# schematic.net
KiCad netlist of a schematic drawn in EAGLE
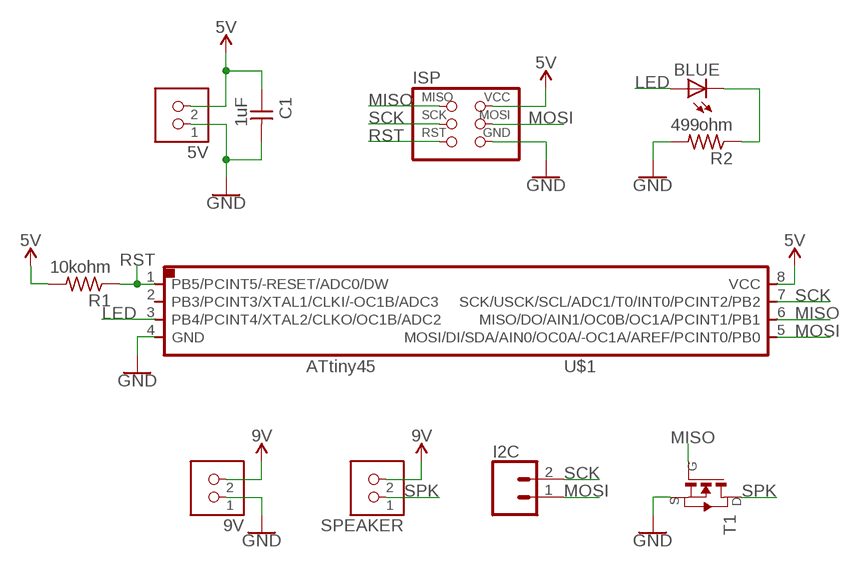
[diagram p0: schematic, sheet 1]

(export (version "E")
  (design (tool "Eeschema 10.0.6"))
  (components
    (comp (ref "5V")
      (value "TERM-1X02-FABLAB")
      (footprint "eagle-import:ED555DS-2DS")
      (libsource (lib "eagle-import") (part "TERM-1X02-FABLAB"))
    )
    (comp (ref "9V")
      (value "TERM-1X02-FABLAB")
      (footprint "eagle-import:ED555DS-2DS")
      (libsource (lib "eagle-import") (part "TERM-1X02-FABLAB"))
    )
    (comp (ref "BLUE")
      (value "LEDFAB1206")
      (footprint "eagle-import:LED1206FAB")
      (libsource (lib "eagle-import") (part "LEDFAB1206"))
    )
    (comp (ref "C1")
      (value "1uF")
      (footprint "eagle-import:C1206FAB")
      (libsource (lib "eagle-import") (part "CAP-UNPOLARIZEDFAB"))
    )
    (comp (ref "I2C")
      (value "CONN_021X02_NO_SILK")
      (footprint "eagle-import:1X02_NO_SILK")
      (libsource (lib "eagle-import") (part "CONN_021X02_NO_SILK"))
    )
    (comp (ref "ISP")
      (value "AVRISPSMD")
      (footprint "eagle-import:2X03SMD")
      (libsource (lib "eagle-import") (part "AVRISPSMD"))
    )
    (comp (ref "R1")
      (value "10kohm")
      (footprint "eagle-import:R1206FAB")
      (libsource (lib "eagle-import") (part "RES-US1206FAB"))
    )
    (comp (ref "R2")
      (value "499ohm")
      (footprint "eagle-import:R1206FAB")
      (libsource (lib "eagle-import") (part "RES-US1206FAB"))
    )
    (comp (ref "SPEAKER")
      (value "TERM-1X02-FABLAB")
      (footprint "eagle-import:ED555DS-2DS")
      (libsource (lib "eagle-import") (part "TERM-1X02-FABLAB"))
    )
    (comp (ref "T1")
      (value "NMOSFETSOT23")
      (footprint "eagle-import:SOT-23")
      (libsource (lib "eagle-import") (part "NMOSFETSOT23"))
    )
    (comp (ref "U$1")
      (value "ATTINY45SI")
      (footprint "eagle-import:SOIC8")
      (libsource (lib "eagle-import") (part "ATTINY45SI"))
    )
  )
  (nets
    (net (code "1") (name "/LED") (class "Default")
      (node (ref "BLUE") (pin "1") (pinfunction "A_1") (pintype "passive"))
      (node (ref "U$1") (pin "3") (pinfunction "PB4/PCINT4/XTAL2/CLKO/OC1B/ADC2_3") (pintype "bidirectional"))
    )
    (net (code "2") (name "/MISO") (class "Default")
      (node (ref "ISP") (pin "1") (pinfunction "MISO_1") (pintype "passive"))
      (node (ref "T1") (pin "3") (pinfunction "G_3") (pintype "passive"))
      (node (ref "U$1") (pin "6") (pinfunction "MISO/DO/AIN1/OC0B/OC1A/PCINT1/PB1_6") (pintype "bidirectional"))
    )
    (net (code "3") (name "/MOSI") (class "Default")
      (node (ref "I2C") (pin "1") (pinfunction "1_1") (pintype "passive"))
      (node (ref "ISP") (pin "4") (pinfunction "MOSI_4") (pintype "passive"))
      (node (ref "U$1") (pin "5") (pinfunction "MOSI/DI/SDA/AIN0/OC0A/-OC1A/AREF/PCINT0/PB0_5") (pintype "bidirectional"))
    )
    (net (code "4") (name "/RST") (class "Default")
      (node (ref "ISP") (pin "5") (pinfunction "RST_5") (pintype "passive"))
      (node (ref "R1") (pin "1") (pinfunction "1_1") (pintype "passive"))
      (node (ref "U$1") (pin "1") (pinfunction "PB5/PCINT5/-RESET/ADC0/DW_1") (pintype "bidirectional"))
    )
    (net (code "5") (name "/SCK") (class "Default")
      (node (ref "I2C") (pin "2") (pinfunction "2_2") (pintype "passive"))
      (node (ref "ISP") (pin "3") (pinfunction "SCK_3") (pintype "passive"))
      (node (ref "U$1") (pin "7") (pinfunction "SCK/USCK/SCL/ADC1/T0/INT0/PCINT2/PB2_7") (pintype "bidirectional"))
    )
    (net (code "6") (name "/SPK") (class "Default")
      (node (ref "SPEAKER") (pin "1") (pinfunction "1_1") (pintype "passive"))
      (node (ref "T1") (pin "1") (pinfunction "D_1") (pintype "passive"))
    )
    (net (code "7") (name "5V") (class "Default")
      (node (ref "5V") (pin "2") (pinfunction "2_2") (pintype "passive"))
      (node (ref "C1") (pin "1") (pinfunction "1_1") (pintype "passive"))
      (node (ref "ISP") (pin "2") (pinfunction "VCC_2") (pintype "passive"))
      (node (ref "R1") (pin "2") (pinfunction "2_2") (pintype "passive"))
      (node (ref "U$1") (pin "8") (pinfunction "VCC_8") (pintype "bidirectional"))
    )
    (net (code "8") (name "9V") (class "Default")
      (node (ref "9V") (pin "2") (pinfunction "2_2") (pintype "passive"))
      (node (ref "SPEAKER") (pin "2") (pinfunction "2_2") (pintype "passive"))
    )
    (net (code "9") (name "GND") (class "Default")
      (node (ref "5V") (pin "1") (pinfunction "1_1") (pintype "passive"))
      (node (ref "9V") (pin "1") (pinfunction "1_1") (pintype "passive"))
      (node (ref "C1") (pin "2") (pinfunction "2_2") (pintype "passive"))
      (node (ref "ISP") (pin "6") (pinfunction "GND_6") (pintype "passive"))
      (node (ref "R2") (pin "2") (pinfunction "2_2") (pintype "passive"))
      (node (ref "T1") (pin "2") (pinfunction "S_2") (pintype "passive"))
      (node (ref "U$1") (pin "4") (pinfunction "GND_4") (pintype "bidirectional"))
    )
    (net (code "10") (name "Net-(BLUE-C)") (class "Default")
      (node (ref "BLUE") (pin "2") (pinfunction "C_2") (pintype "passive"))
      (node (ref "R2") (pin "1") (pinfunction "1_1") (pintype "passive"))
    )
    (net (code "11") (name "unconnected-(U$1-PB3{slash}PCINT3{slash}XTAL1{slash}CLKI{slash}-OC1B{slash}ADC3-Pad2)") (class "Default")
      (node (ref "U$1") (pin "2") (pinfunction "PB3/PCINT3/XTAL1/CLKI/-OC1B/ADC3_2") (pintype "bidirectional"))
    )
  )
)
